# qspi_flash.net
KiCad netlist of a schematic drawn in Altium Designer
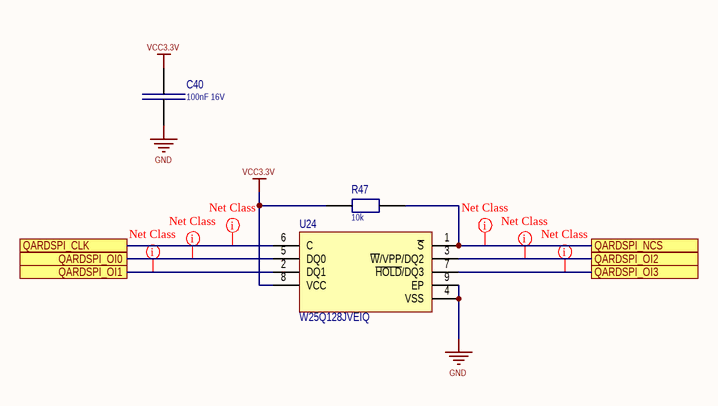
[diagram p0: qspi_flash.schdoc]

(export (version "E")
  (design (tool "Eeschema 10.0.6"))
  (components
    (comp (ref "C40")
      (value "100nF 16V")
      (footprint "C_0603")
      (description "Capacitor")
      (fields (field (name "PART NUMBER") "CC0603KPX7R9BB104"))
      (libsource (lib "AX_Altium_v2.3") (part "C0603"))
    )
    (comp (ref "R47")
      (value "10k")
      (footprint "R_0603")
      (description "Resistor")
      (fields (field (name "PART NUMBER") "RC0603FR-0710KL"))
      (libsource (lib "resistors") (part "RES_SMD"))
    )
    (comp (ref "U24")
      (value "W25Q128JVEIQ")
      (footprint "W-PDFN-8 (MLP8) – 8mm ? 6mm  Se")
      (description "Flash Memory")
      (libsource (lib "AX_Altium_v2.3") (part "MT25QL********W9-0SIT"))
    )
  )
  (nets
    (net (code "1") (name "/QARDSPI_CLK") (class "Default")
      (node (ref "U24") (pin "6") (pinfunction "C_6") (pintype "passive"))
    )
    (net (code "2") (name "/QARDSPI_NCS") (class "Default")
      (node (ref "R47") (pin "2") (pinfunction "2_2") (pintype "passive"))
      (node (ref "U24") (pin "1") (pinfunction "~{S}_1") (pintype "passive"))
    )
    (net (code "3") (name "/QARDSPI_OI0") (class "Default")
      (node (ref "U24") (pin "5") (pinfunction "DQ0_5") (pintype "passive"))
    )
    (net (code "4") (name "/QARDSPI_OI1") (class "Default")
      (node (ref "U24") (pin "2") (pinfunction "DQ1_2") (pintype "passive"))
    )
    (net (code "5") (name "/QARDSPI_OI2") (class "Default")
      (node (ref "U24") (pin "3") (pinfunction "~{W}/VPP/DQ2_3") (pintype "passive"))
    )
    (net (code "6") (name "/QARDSPI_OI3") (class "Default")
      (node (ref "U24") (pin "7") (pinfunction "~{HOLD}/DQ3_7") (pintype "passive"))
    )
    (net (code "7") (name "GND") (class "Default")
      (node (ref "C40") (pin "1") (pinfunction "1_1") (pintype "passive"))
      (node (ref "U24") (pin "4") (pinfunction "VSS_4") (pintype "passive"))
      (node (ref "U24") (pin "9") (pinfunction "EP_9") (pintype "passive"))
    )
    (net (code "8") (name "VCC3.3V") (class "Default")
      (node (ref "C40") (pin "2") (pinfunction "2_2") (pintype "passive"))
      (node (ref "R47") (pin "1") (pinfunction "1_1") (pintype "passive"))
      (node (ref "U24") (pin "8") (pinfunction "VCC_8") (pintype "passive"))
    )
  )
)
